# SKF.net
KiCad netlist of a schematic drawn in Altium Designer
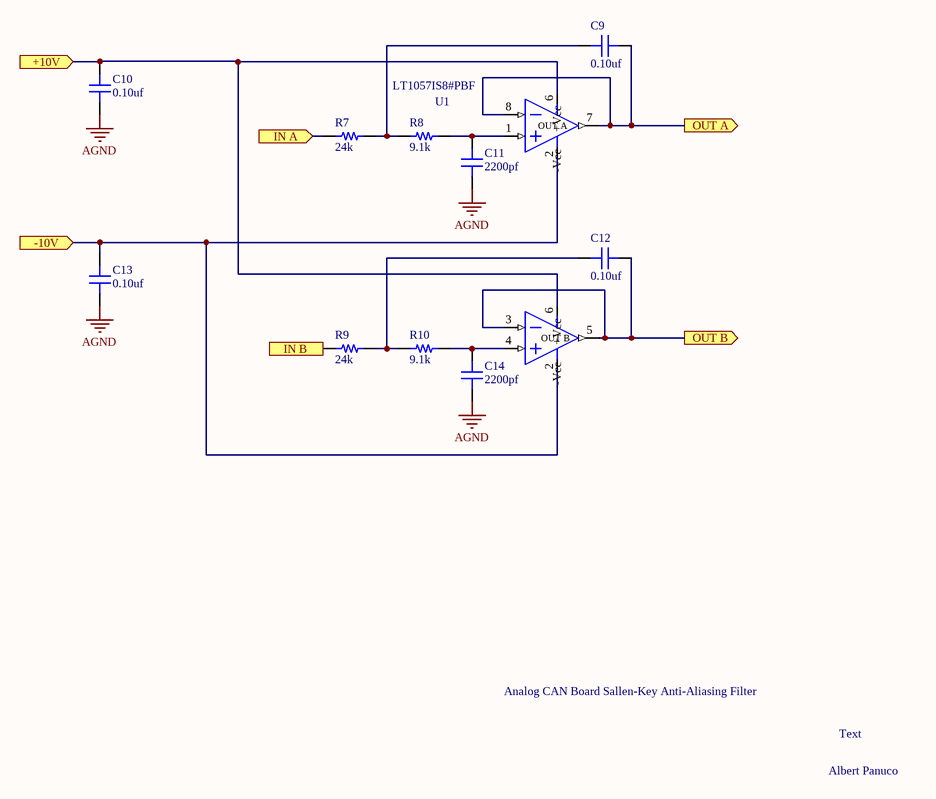
[diagram p0: SKF.SchDoc]

(export (version "E")
  (design (tool "Eeschema 10.0.6"))
  (components
    (comp (ref "C9")
      (value "0.10uf")
      (footprint "CAP 0805/2012")
      (fields
        (field (name "Comment") "Capacitor MLCC 0.10uf 25V CAP 0805/2012")
        (field (name "CREATED_BY") "Nick Mah")
      )
      (libsource (lib "Altium-Lib") (part "Capacitor"))
    )
    (comp (ref "C10")
      (value "0.10uf")
      (footprint "CAP 0805/2012")
      (fields
        (field (name "Comment") "Capacitor MLCC 0.10uf 25V CAP 0805/2012")
        (field (name "CREATED_BY") "Nick Mah")
      )
      (libsource (lib "Altium-Lib") (part "Capacitor"))
    )
    (comp (ref "C11")
      (value "2200pf")
      (footprint "CAP 0805/2012")
      (fields
        (field (name "Comment") "Capacitor MLCC 2200pf 25V CAP 0805/2012")
        (field (name "CREATED_BY") "Nick Mah")
      )
      (libsource (lib "Altium-Lib") (part "Capacitor"))
    )
    (comp (ref "C12")
      (value "0.10uf")
      (footprint "CAP 0805/2012")
      (fields
        (field (name "Comment") "Capacitor MLCC 0.10uf 25V CAP 0805/2012")
        (field (name "CREATED_BY") "Nick Mah")
      )
      (libsource (lib "Altium-Lib") (part "Capacitor"))
    )
    (comp (ref "C13")
      (value "0.10uf")
      (footprint "CAP 0805/2012")
      (fields
        (field (name "Comment") "Capacitor MLCC 0.10uf 25V CAP 0805/2012")
        (field (name "CREATED_BY") "Nick Mah")
      )
      (libsource (lib "Altium-Lib") (part "Capacitor"))
    )
    (comp (ref "C14")
      (value "2200pf")
      (footprint "CAP 0805/2012")
      (fields
        (field (name "Comment") "Capacitor MLCC 2200pf 25V CAP 0805/2012")
        (field (name "CREATED_BY") "Nick Mah")
      )
      (libsource (lib "Altium-Lib") (part "Capacitor"))
    )
    (comp (ref "R7")
      (value "24k")
      (footprint "RES 0805/2012")
      (fields
        (field (name "TOLERANCE") "1%")
        (field (name "POWER") "1/10W")
        (field (name "Comment") "Resistor 24k 0805 1/10W 1%")
        (field (name "CREATED_BY") "Nick Mah")
      )
      (libsource (lib "Altium-Lib") (part "Resistor"))
    )
    (comp (ref "R8")
      (value "9.1k")
      (footprint "RES 0805/2012")
      (fields
        (field (name "TOLERANCE") "1%")
        (field (name "POWER") "1/10W")
        (field (name "Comment") "Resistor 9.1k 0805 1/10W 1%")
        (field (name "CREATED_BY") "Nick Mah")
      )
      (libsource (lib "Altium-Lib") (part "Resistor"))
    )
    (comp (ref "R9")
      (value "24k")
      (footprint "RES 0805/2012")
      (fields
        (field (name "TOLERANCE") "1%")
        (field (name "POWER") "1/10W")
        (field (name "Comment") "Resistor 24k 0805 1/10W 1%")
        (field (name "CREATED_BY") "Nick Mah")
      )
      (libsource (lib "Altium-Lib") (part "Resistor"))
    )
    (comp (ref "R10")
      (value "9.1k")
      (footprint "RES 0805/2012")
      (fields
        (field (name "TOLERANCE") "1%")
        (field (name "POWER") "1/10W")
        (field (name "Comment") "Resistor 9.1k 0805 1/10W 1%")
        (field (name "CREATED_BY") "Nick Mah")
      )
      (libsource (lib "Altium-Lib") (part "Resistor"))
    )
    (comp (ref "U1")
      (value "LT1057IS8#PBF")
      (footprint "SOIC-8")
      (description "IC OPAMP JFET 5MHZ 8SO")
      (fields (field (name "CREATED_BY") "Albert Panuco"))
      (libsource (lib "Altium-Lib") (part "LT1057IS8#PBF"))
    )
  )
  (nets
    (net (code "1") (name "/+10V") (class "Default")
      (node (ref "C10") (pin "2") (pinfunction "2_2") (pintype "passive"))
      (node (ref "U1") (pin "6") (pinfunction "+Vcc_6") (pintype "input"))
    )
    (net (code "2") (name "/-10V") (class "Default")
      (node (ref "C13") (pin "1") (pinfunction "1_1") (pintype "passive"))
      (node (ref "U1") (pin "2") (pinfunction "-Vcc_2") (pintype "input"))
    )
    (net (code "3") (name "/IN A") (class "Default")
      (node (ref "R7") (pin "1") (pinfunction "1_1") (pintype "passive"))
    )
    (net (code "4") (name "/IN B") (class "Default")
      (node (ref "R9") (pin "1") (pinfunction "1_1") (pintype "passive"))
    )
    (net (code "5") (name "/OUT A") (class "Default")
      (node (ref "C9") (pin "2") (pinfunction "2_2") (pintype "passive"))
      (node (ref "U1") (pin "7") (pinfunction "OUT_A_7") (pintype "output"))
      (node (ref "U1") (pin "8") (pinfunction "-IN_A_8") (pintype "input"))
    )
    (net (code "6") (name "/OUT B") (class "Default")
      (node (ref "C12") (pin "2") (pinfunction "2_2") (pintype "passive"))
      (node (ref "U1") (pin "3") (pinfunction "+IN_B_3") (pintype "input"))
      (node (ref "U1") (pin "5") (pinfunction "OUT_B_5") (pintype "output"))
    )
    (net (code "7") (name "AGND") (class "Default")
      (node (ref "C10") (pin "1") (pinfunction "1_1") (pintype "passive"))
      (node (ref "C11") (pin "1") (pinfunction "1_1") (pintype "passive"))
      (node (ref "C13") (pin "2") (pinfunction "2_2") (pintype "passive"))
      (node (ref "C14") (pin "1") (pinfunction "1_1") (pintype "passive"))
    )
    (net (code "8") (name "Net-(C9-Pad1)") (class "Default")
      (node (ref "C9") (pin "1") (pinfunction "1_1") (pintype "passive"))
      (node (ref "R7") (pin "2") (pinfunction "2_2") (pintype "passive"))
      (node (ref "R8") (pin "1") (pinfunction "1_1") (pintype "passive"))
    )
    (net (code "9") (name "Net-(C12-Pad1)") (class "Default")
      (node (ref "C12") (pin "1") (pinfunction "1_1") (pintype "passive"))
      (node (ref "R10") (pin "1") (pinfunction "1_1") (pintype "passive"))
      (node (ref "R9") (pin "2") (pinfunction "2_2") (pintype "passive"))
    )
    (net (code "10") (name "Net-(C14-Pad2)") (class "Default")
      (node (ref "C14") (pin "2") (pinfunction "2_2") (pintype "passive"))
      (node (ref "R10") (pin "2") (pinfunction "2_2") (pintype "passive"))
      (node (ref "U1") (pin "4") (pinfunction "+IN_B_4") (pintype "input"))
    )
    (net (code "11") (name "Net-(U1-+IN_A)") (class "Default")
      (node (ref "C11") (pin "2") (pinfunction "2_2") (pintype "passive"))
      (node (ref "R8") (pin "2") (pinfunction "2_2") (pintype "passive"))
      (node (ref "U1") (pin "1") (pinfunction "+IN_A_1") (pintype "input"))
    )
  )
)
